# led-controller-board.net
KiCad netlist of a schematic drawn in EAGLE
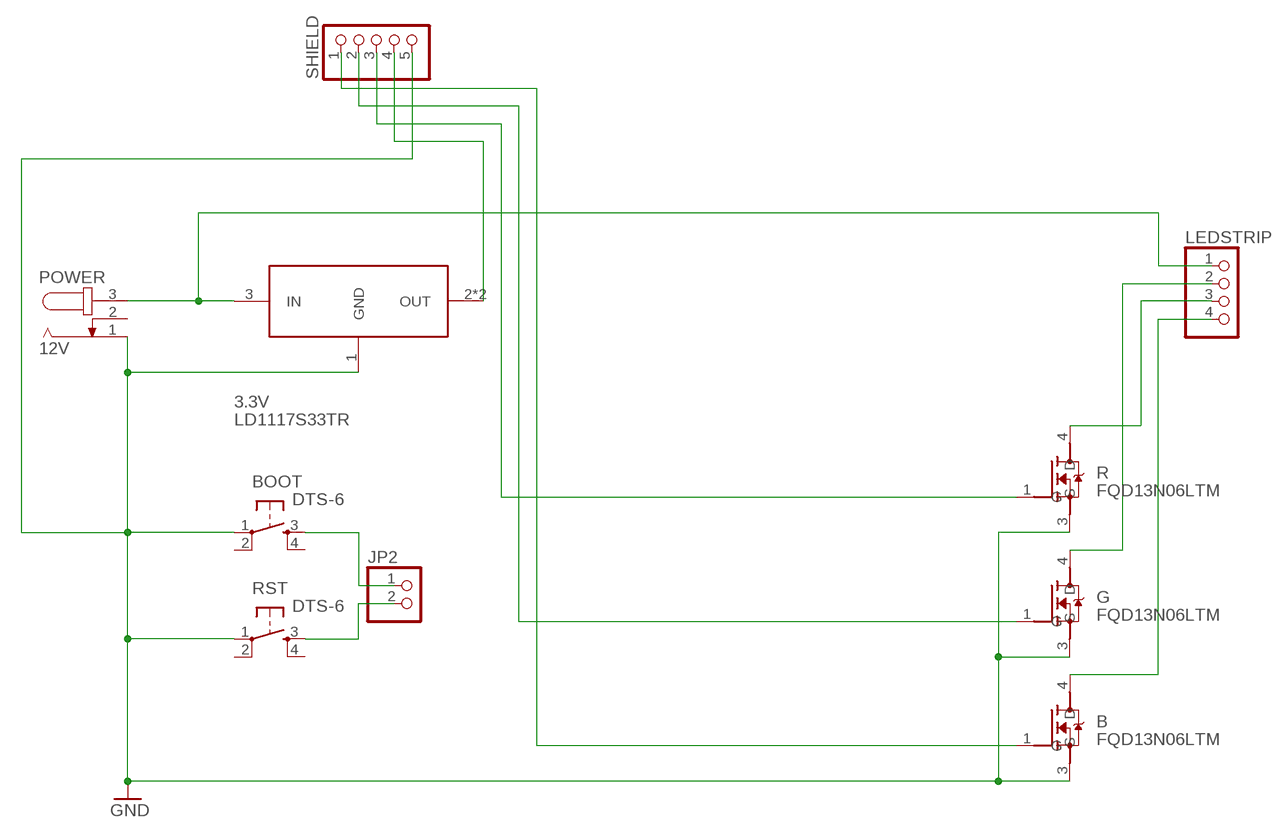
[diagram p0: schematic, sheet 1]

(export (version "E")
  (design (tool "Eeschema 10.0.6"))
  (components
    (comp (ref "3.3V")
      (value "LD1117S33TR")
      (footprint "eagle-import:SOT223")
      (fields (field (name "MF") "STMicroelectronics"))
      (libsource (lib "eagle-import") (part "LD1117S33TR"))
    )
    (comp (ref "B")
      (value "FQD13N06LTM")
      (footprint "eagle-import:TO229P991X239-3N")
      (fields (field (name "MF") "Fairchild Semiconductor"))
      (libsource (lib "eagle-import") (part "FQD13N06LTM"))
    )
    (comp (ref "BOOT")
      (value "DTS-6")
      (footprint "eagle-import:DTS-6")
      (libsource (lib "eagle-import") (part "DTS-6"))
    )
    (comp (ref "G")
      (value "FQD13N06LTM")
      (footprint "eagle-import:TO229P991X239-3N")
      (fields (field (name "MF") "Fairchild Semiconductor"))
      (libsource (lib "eagle-import") (part "FQD13N06LTM"))
    )
    (comp (ref "JP2")
      (value "PINHD-1X2")
      (footprint "eagle-import:1X02")
      (libsource (lib "eagle-import") (part "PINHD-1X2"))
    )
    (comp (ref "LEDSTRIP")
      (value "PINHD-1X4/90")
      (footprint "eagle-import:1X04_90")
      (libsource (lib "eagle-import") (part "PINHD-1X4/90"))
    )
    (comp (ref "POWER")
      (value "12V")
      (footprint "eagle-import:SPC4078")
      (libsource (lib "eagle-import") (part "JACK-PLUG1"))
    )
    (comp (ref "R")
      (value "FQD13N06LTM")
      (footprint "eagle-import:TO229P991X239-3N")
      (fields (field (name "MF") "Fairchild Semiconductor"))
      (libsource (lib "eagle-import") (part "FQD13N06LTM"))
    )
    (comp (ref "RST")
      (value "DTS-6")
      (footprint "eagle-import:DTS-6")
      (libsource (lib "eagle-import") (part "DTS-6"))
    )
    (comp (ref "SHIELD")
      (value "PINHD-1X5")
      (footprint "eagle-import:1X05")
      (libsource (lib "eagle-import") (part "PINHD-1X5"))
    )
  )
  (nets
    (net (code "1") (name "GND") (class "Default")
      (node (ref "3.3V") (pin "1") (pinfunction "GND_1") (pintype "passive"))
      (node (ref "B") (pin "3") (pinfunction "S_3") (pintype "passive"))
      (node (ref "BOOT") (pin "1") (pinfunction "1_1") (pintype "passive"))
      (node (ref "G") (pin "3") (pinfunction "S_3") (pintype "passive"))
      (node (ref "POWER") (pin "1") (pinfunction "1_1") (pintype "passive"))
      (node (ref "R") (pin "3") (pinfunction "S_3") (pintype "passive"))
      (node (ref "RST") (pin "1") (pinfunction "1_1") (pintype "passive"))
      (node (ref "SHIELD") (pin "5") (pinfunction "5_5") (pintype "passive"))
    )
    (net (code "2") (name "Net-(3.3V-IN)") (class "Default")
      (node (ref "3.3V") (pin "3") (pinfunction "IN_3") (pintype "input"))
      (node (ref "LEDSTRIP") (pin "1") (pinfunction "1_1") (pintype "passive"))
      (node (ref "POWER") (pin "3") (pinfunction "3_3") (pintype "passive"))
    )
    (net (code "3") (name "Net-(3.3V-OUT-Pad2)") (class "Default")
      (node (ref "3.3V") (pin "2") (pinfunction "OUT_2") (pintype "output"))
      (node (ref "3.3V") (pin "4") (pinfunction "OUT_4") (pintype "output"))
      (node (ref "SHIELD") (pin "4") (pinfunction "4_4") (pintype "passive"))
    )
    (net (code "4") (name "Net-(B-D)") (class "Default")
      (node (ref "B") (pin "4") (pinfunction "D_4") (pintype "passive"))
      (node (ref "LEDSTRIP") (pin "4") (pinfunction "4_4") (pintype "passive"))
    )
    (net (code "5") (name "Net-(B-G)") (class "Default")
      (node (ref "B") (pin "1") (pinfunction "G_1") (pintype "passive"))
      (node (ref "SHIELD") (pin "1") (pinfunction "1_1") (pintype "passive"))
    )
    (net (code "6") (name "Net-(BOOT-Pad3)") (class "Default")
      (node (ref "BOOT") (pin "3") (pinfunction "3_3") (pintype "passive"))
      (node (ref "JP2") (pin "1") (pinfunction "1_1") (pintype "passive"))
    )
    (net (code "7") (name "Net-(G-D)") (class "Default")
      (node (ref "G") (pin "4") (pinfunction "D_4") (pintype "passive"))
      (node (ref "LEDSTRIP") (pin "2") (pinfunction "2_2") (pintype "passive"))
    )
    (net (code "8") (name "Net-(G-G)") (class "Default")
      (node (ref "G") (pin "1") (pinfunction "G_1") (pintype "passive"))
      (node (ref "SHIELD") (pin "2") (pinfunction "2_2") (pintype "passive"))
    )
    (net (code "9") (name "Net-(JP2-Pad2)") (class "Default")
      (node (ref "JP2") (pin "2") (pinfunction "2_2") (pintype "passive"))
      (node (ref "RST") (pin "3") (pinfunction "3_3") (pintype "passive"))
    )
    (net (code "10") (name "Net-(R-D)") (class "Default")
      (node (ref "LEDSTRIP") (pin "3") (pinfunction "3_3") (pintype "passive"))
      (node (ref "R") (pin "4") (pinfunction "D_4") (pintype "passive"))
    )
    (net (code "11") (name "Net-(R-G)") (class "Default")
      (node (ref "R") (pin "1") (pinfunction "G_1") (pintype "passive"))
      (node (ref "SHIELD") (pin "3") (pinfunction "3_3") (pintype "passive"))
    )
    (net (code "12") (name "unconnected-(BOOT-Pad2)") (class "Default")
      (node (ref "BOOT") (pin "2") (pinfunction "2_2") (pintype "passive"))
    )
    (net (code "13") (name "unconnected-(BOOT-Pad4)") (class "Default")
      (node (ref "BOOT") (pin "4") (pinfunction "4_4") (pintype "passive"))
    )
    (net (code "14") (name "unconnected-(POWER-Pad2)") (class "Default")
      (node (ref "POWER") (pin "2") (pinfunction "2_2") (pintype "passive"))
    )
    (net (code "15") (name "unconnected-(RST-Pad2)") (class "Default")
      (node (ref "RST") (pin "2") (pinfunction "2_2") (pintype "passive"))
    )
    (net (code "16") (name "unconnected-(RST-Pad4)") (class "Default")
      (node (ref "RST") (pin "4") (pinfunction "4_4") (pintype "passive"))
    )
  )
)
